# TFT_Ticketing_Master.net
KiCad netlist of a schematic drawn in Altium Designer
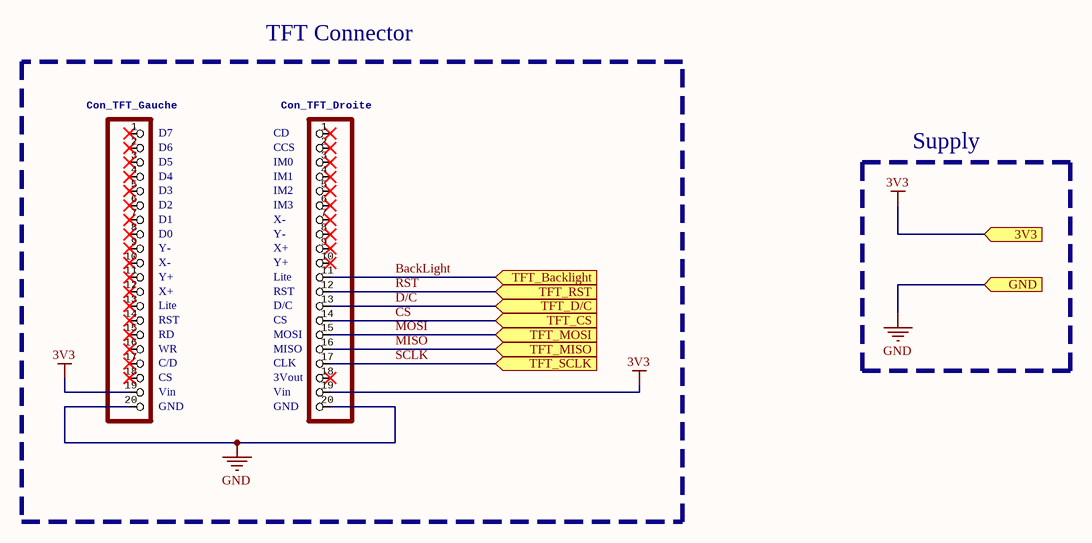
[diagram p0: TFT_Ticketing_Master.SchDoc]

(export (version "E")
  (design (tool "Eeschema 10.0.6"))
  (components
    (comp (ref "Con_TFT_Droite")
      (value "HEADER-1X20ROUND")
      (footprint "HDR1X20")
      (libsource (lib "microbuilder") (part "HEADER-1X20ROUND"))
    )
    (comp (ref "Con_TFT_Gauche")
      (value "HEADER-1X20ROUND")
      (footprint "HDR1X20")
      (libsource (lib "microbuilder") (part "HEADER-1X20ROUND"))
    )
  )
  (nets
    (net (code "1") (name "/BackLight") (class "Default")
      (node (ref "Con_TFT_Droite") (pin "11") (pinfunction "11_11") (pintype "passive"))
    )
    (net (code "2") (name "/CS") (class "Default")
      (node (ref "Con_TFT_Droite") (pin "14") (pinfunction "14_14") (pintype "passive"))
    )
    (net (code "3") (name "/D{slash}C") (class "Default")
      (node (ref "Con_TFT_Droite") (pin "13") (pinfunction "13_13") (pintype "passive"))
    )
    (net (code "4") (name "/MISO") (class "Default")
      (node (ref "Con_TFT_Droite") (pin "16") (pinfunction "16_16") (pintype "passive"))
    )
    (net (code "5") (name "/MOSI") (class "Default")
      (node (ref "Con_TFT_Droite") (pin "15") (pinfunction "15_15") (pintype "passive"))
    )
    (net (code "6") (name "/RST") (class "Default")
      (node (ref "Con_TFT_Droite") (pin "12") (pinfunction "12_12") (pintype "passive"))
    )
    (net (code "7") (name "/SCLK") (class "Default")
      (node (ref "Con_TFT_Droite") (pin "17") (pinfunction "17_17") (pintype "passive"))
    )
    (net (code "8") (name "3V3") (class "Default")
      (node (ref "Con_TFT_Droite") (pin "19") (pinfunction "19_19") (pintype "passive"))
      (node (ref "Con_TFT_Gauche") (pin "19") (pinfunction "19_19") (pintype "passive"))
    )
    (net (code "9") (name "GND") (class "Default")
      (node (ref "Con_TFT_Droite") (pin "20") (pinfunction "20_20") (pintype "passive"))
      (node (ref "Con_TFT_Gauche") (pin "20") (pinfunction "20_20") (pintype "passive"))
    )
    (net (code "10") (name "unconnected-(Con_TFT_Droite-Pad1)") (class "Default")
      (node (ref "Con_TFT_Droite") (pin "1") (pinfunction "1_1") (pintype "passive+no_connect"))
    )
    (net (code "11") (name "unconnected-(Con_TFT_Droite-Pad2)") (class "Default")
      (node (ref "Con_TFT_Droite") (pin "2") (pinfunction "2_2") (pintype "passive+no_connect"))
    )
    (net (code "12") (name "unconnected-(Con_TFT_Droite-Pad3)") (class "Default")
      (node (ref "Con_TFT_Droite") (pin "3") (pinfunction "3_3") (pintype "passive+no_connect"))
    )
    (net (code "13") (name "unconnected-(Con_TFT_Droite-Pad4)") (class "Default")
      (node (ref "Con_TFT_Droite") (pin "4") (pinfunction "4_4") (pintype "passive+no_connect"))
    )
    (net (code "14") (name "unconnected-(Con_TFT_Droite-Pad5)") (class "Default")
      (node (ref "Con_TFT_Droite") (pin "5") (pinfunction "5_5") (pintype "passive+no_connect"))
    )
    (net (code "15") (name "unconnected-(Con_TFT_Droite-Pad6)") (class "Default")
      (node (ref "Con_TFT_Droite") (pin "6") (pinfunction "6_6") (pintype "passive+no_connect"))
    )
    (net (code "16") (name "unconnected-(Con_TFT_Droite-Pad7)") (class "Default")
      (node (ref "Con_TFT_Droite") (pin "7") (pinfunction "7_7") (pintype "passive+no_connect"))
    )
    (net (code "17") (name "unconnected-(Con_TFT_Droite-Pad8)") (class "Default")
      (node (ref "Con_TFT_Droite") (pin "8") (pinfunction "8_8") (pintype "passive+no_connect"))
    )
    (net (code "18") (name "unconnected-(Con_TFT_Droite-Pad9)") (class "Default")
      (node (ref "Con_TFT_Droite") (pin "9") (pinfunction "9_9") (pintype "passive+no_connect"))
    )
    (net (code "19") (name "unconnected-(Con_TFT_Droite-Pad10)") (class "Default")
      (node (ref "Con_TFT_Droite") (pin "10") (pinfunction "10_10") (pintype "passive+no_connect"))
    )
    (net (code "20") (name "unconnected-(Con_TFT_Droite-Pad18)") (class "Default")
      (node (ref "Con_TFT_Droite") (pin "18") (pinfunction "18_18") (pintype "passive+no_connect"))
    )
    (net (code "21") (name "unconnected-(Con_TFT_Gauche-Pad1)") (class "Default")
      (node (ref "Con_TFT_Gauche") (pin "1") (pinfunction "1_1") (pintype "passive+no_connect"))
    )
    (net (code "22") (name "unconnected-(Con_TFT_Gauche-Pad2)") (class "Default")
      (node (ref "Con_TFT_Gauche") (pin "2") (pinfunction "2_2") (pintype "passive+no_connect"))
    )
    (net (code "23") (name "unconnected-(Con_TFT_Gauche-Pad3)") (class "Default")
      (node (ref "Con_TFT_Gauche") (pin "3") (pinfunction "3_3") (pintype "passive+no_connect"))
    )
    (net (code "24") (name "unconnected-(Con_TFT_Gauche-Pad4)") (class "Default")
      (node (ref "Con_TFT_Gauche") (pin "4") (pinfunction "4_4") (pintype "passive+no_connect"))
    )
    (net (code "25") (name "unconnected-(Con_TFT_Gauche-Pad5)") (class "Default")
      (node (ref "Con_TFT_Gauche") (pin "5") (pinfunction "5_5") (pintype "passive+no_connect"))
    )
    (net (code "26") (name "unconnected-(Con_TFT_Gauche-Pad6)") (class "Default")
      (node (ref "Con_TFT_Gauche") (pin "6") (pinfunction "6_6") (pintype "passive+no_connect"))
    )
    (net (code "27") (name "unconnected-(Con_TFT_Gauche-Pad7)") (class "Default")
      (node (ref "Con_TFT_Gauche") (pin "7") (pinfunction "7_7") (pintype "passive+no_connect"))
    )
    (net (code "28") (name "unconnected-(Con_TFT_Gauche-Pad8)") (class "Default")
      (node (ref "Con_TFT_Gauche") (pin "8") (pinfunction "8_8") (pintype "passive+no_connect"))
    )
    (net (code "29") (name "unconnected-(Con_TFT_Gauche-Pad9)") (class "Default")
      (node (ref "Con_TFT_Gauche") (pin "9") (pinfunction "9_9") (pintype "passive+no_connect"))
    )
    (net (code "30") (name "unconnected-(Con_TFT_Gauche-Pad10)") (class "Default")
      (node (ref "Con_TFT_Gauche") (pin "10") (pinfunction "10_10") (pintype "passive+no_connect"))
    )
    (net (code "31") (name "unconnected-(Con_TFT_Gauche-Pad11)") (class "Default")
      (node (ref "Con_TFT_Gauche") (pin "11") (pinfunction "11_11") (pintype "passive+no_connect"))
    )
    (net (code "32") (name "unconnected-(Con_TFT_Gauche-Pad12)") (class "Default")
      (node (ref "Con_TFT_Gauche") (pin "12") (pinfunction "12_12") (pintype "passive+no_connect"))
    )
    (net (code "33") (name "unconnected-(Con_TFT_Gauche-Pad13)") (class "Default")
      (node (ref "Con_TFT_Gauche") (pin "13") (pinfunction "13_13") (pintype "passive+no_connect"))
    )
    (net (code "34") (name "unconnected-(Con_TFT_Gauche-Pad14)") (class "Default")
      (node (ref "Con_TFT_Gauche") (pin "14") (pinfunction "14_14") (pintype "passive+no_connect"))
    )
    (net (code "35") (name "unconnected-(Con_TFT_Gauche-Pad15)") (class "Default")
      (node (ref "Con_TFT_Gauche") (pin "15") (pinfunction "15_15") (pintype "passive+no_connect"))
    )
    (net (code "36") (name "unconnected-(Con_TFT_Gauche-Pad16)") (class "Default")
      (node (ref "Con_TFT_Gauche") (pin "16") (pinfunction "16_16") (pintype "passive+no_connect"))
    )
    (net (code "37") (name "unconnected-(Con_TFT_Gauche-Pad17)") (class "Default")
      (node (ref "Con_TFT_Gauche") (pin "17") (pinfunction "17_17") (pintype "passive+no_connect"))
    )
    (net (code "38") (name "unconnected-(Con_TFT_Gauche-Pad18)") (class "Default")
      (node (ref "Con_TFT_Gauche") (pin "18") (pinfunction "18_18") (pintype "passive+no_connect"))
    )
  )
)
